# TK531_Utgangstrinn.net
KiCad netlist of a schematic drawn in Altium Designer
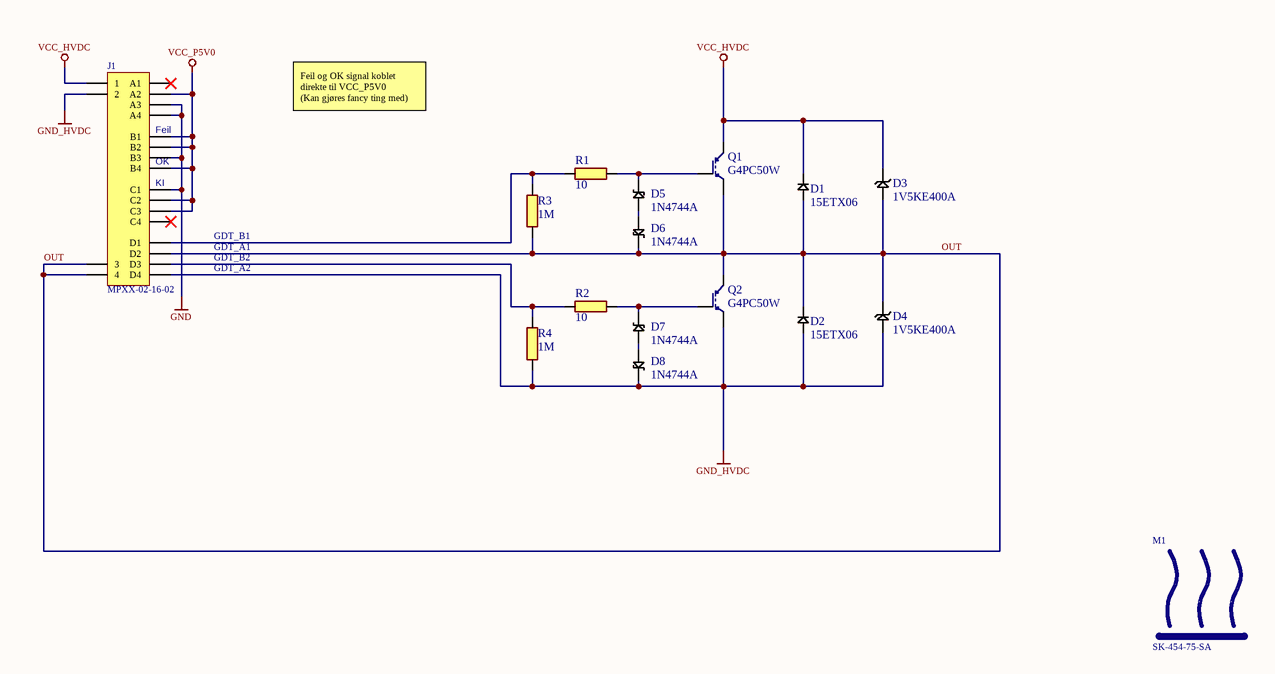
[diagram p0: TK531_Utgangstrinn.SchDoc]

(export (version "E")
  (design (tool "Eeschema 10.0.6"))
  (components
    (comp (ref "D1")
      (value "15ETX06")
      (footprint "TO-220-2P")
      (description "DIODE, HYPERFAST, 15A, 600V")
      (libsource (lib "OVLib_64") (part "Diode_3P"))
    )
    (comp (ref "D2")
      (value "15ETX06")
      (footprint "TO-220-2P")
      (description "DIODE, HYPERFAST, 15A, 600V")
      (libsource (lib "OVLib_64") (part "Diode_3P"))
    )
    (comp (ref "D3")
      (value "1V5KE400A")
      (footprint "DO-201")
      (description "TVS diode,  400V, 1500W")
      (libsource (lib "OVLib_64") (part "TVSDiode"))
    )
    (comp (ref "D4")
      (value "1V5KE400A")
      (footprint "DO-201")
      (description "TVS diode,  400V, 1500W")
      (libsource (lib "OVLib_64") (part "TVSDiode"))
    )
    (comp (ref "D5")
      (value "1N4744A")
      (footprint "DO-41")
      (description "Zenerdiode 15V 1.3W")
      (libsource (lib "OVLib_64") (part "Zenerdiode"))
    )
    (comp (ref "D6")
      (value "1N4744A")
      (footprint "DO-41")
      (description "Zenerdiode 15V 1.3W")
      (libsource (lib "OVLib_64") (part "Zenerdiode"))
    )
    (comp (ref "D7")
      (value "1N4744A")
      (footprint "DO-41")
      (description "Zenerdiode 15V 1.3W")
      (libsource (lib "OVLib_64") (part "Zenerdiode"))
    )
    (comp (ref "D8")
      (value "1N4744A")
      (footprint "DO-41")
      (description "Zenerdiode 15V 1.3W")
      (libsource (lib "OVLib_64") (part "Zenerdiode"))
    )
    (comp (ref "J1")
      (value "MPXX-02-16-02")
      (footprint "MPTC-02-16-02-01-03-L-RA-SD")
      (description "SAMTEC Connector")
      (libsource (lib "OVLib_64") (part "MPXX-02-16-02"))
    )
    (comp (ref "M1")
      (value "SK-454-75-SA")
      (footprint "SK-454-75-SA")
      (description "Heatsink")
      (libsource (lib "OVLib_64") (part "Heatsink"))
    )
    (comp (ref "Q1")
      (value "G4PC50W")
      (footprint "TO-247")
      (description "IGBT, 600V, 55A")
      (libsource (lib "OVLib_64") (part "G4PC50W"))
    )
    (comp (ref "Q2")
      (value "G4PC50W")
      (footprint "TO-247")
      (description "IGBT, 600V, 55A")
      (libsource (lib "OVLib_64") (part "G4PC50W"))
    )
    (comp (ref "R1")
      (value "10")
      (footprint "RESA_0.25W")
      (description "0.25W 1% Generic resistor")
      (libsource (lib "") (part "Resistor2_1"))
    )
    (comp (ref "R2")
      (value "10")
      (footprint "RESA_0.25W")
      (description "0.25W 1% Generic resistor")
      (libsource (lib "") (part "Resistor2_1"))
    )
    (comp (ref "R3")
      (value "1M")
      (footprint "RESC0603(1608)_N")
      (description "0.1W 1% Thick film resistor")
      (libsource (lib "OVLib_64") (part "Resistor2"))
    )
    (comp (ref "R4")
      (value "1M")
      (footprint "RESC0603(1608)_N")
      (description "0.1W 1% Thick film resistor")
      (libsource (lib "OVLib_64") (part "Resistor2"))
    )
  )
  (nets
    (net (code "1") (name "/OUT") (class "Default")
      (node (ref "D1") (pin "3") (pinfunction "A_3") (pintype "passive"))
      (node (ref "D2") (pin "1") (pinfunction "K_1") (pintype "passive"))
      (node (ref "D3") (pin "1") (pinfunction "A_1") (pintype "passive"))
      (node (ref "D4") (pin "2") (pinfunction "K_2") (pintype "passive"))
      (node (ref "D6") (pin "2") (pinfunction "K_2") (pintype "passive"))
      (node (ref "J1") (pin "18") (pinfunction "D2_18") (pintype "passive"))
      (node (ref "J1") (pin "3") (pinfunction "3_3") (pintype "passive"))
      (node (ref "J1") (pin "4") (pinfunction "4_4") (pintype "passive"))
      (node (ref "Q1") (pin "3") (pinfunction "E_3") (pintype "passive"))
      (node (ref "Q2") (pin "2") (pinfunction "C_2") (pintype "passive"))
      (node (ref "R3") (pin "1") (pinfunction "1_1") (pintype "passive"))
    )
    (net (code "2") (name "GND") (class "Default")
      (node (ref "J1") (pin "11") (pinfunction "B3_11") (pintype "passive"))
      (node (ref "J1") (pin "13") (pinfunction "C1_13") (pintype "passive"))
      (node (ref "J1") (pin "7") (pinfunction "A3_7") (pintype "passive"))
      (node (ref "J1") (pin "8") (pinfunction "A4_8") (pintype "passive"))
    )
    (net (code "3") (name "GND_HVDC") (class "Default")
      (node (ref "D2") (pin "3") (pinfunction "A_3") (pintype "passive"))
      (node (ref "D4") (pin "1") (pinfunction "A_1") (pintype "passive"))
      (node (ref "D8") (pin "2") (pinfunction "K_2") (pintype "passive"))
      (node (ref "J1") (pin "2") (pinfunction "2_2") (pintype "passive"))
      (node (ref "J1") (pin "20") (pinfunction "D4_20") (pintype "passive"))
      (node (ref "Q2") (pin "3") (pinfunction "E_3") (pintype "passive"))
      (node (ref "R4") (pin "1") (pinfunction "1_1") (pintype "passive"))
    )
    (net (code "4") (name "Net-(D5-A)") (class "Default")
      (node (ref "D5") (pin "1") (pinfunction "A_1") (pintype "passive"))
      (node (ref "D6") (pin "1") (pinfunction "A_1") (pintype "passive"))
    )
    (net (code "5") (name "Net-(D5-K)") (class "Default")
      (node (ref "D5") (pin "2") (pinfunction "K_2") (pintype "passive"))
      (node (ref "Q1") (pin "1") (pinfunction "G_1") (pintype "passive"))
      (node (ref "R1") (pin "2") (pinfunction "2_2") (pintype "passive"))
    )
    (net (code "6") (name "Net-(D7-A)") (class "Default")
      (node (ref "D7") (pin "1") (pinfunction "A_1") (pintype "passive"))
      (node (ref "D8") (pin "1") (pinfunction "A_1") (pintype "passive"))
    )
    (net (code "7") (name "Net-(D7-K)") (class "Default")
      (node (ref "D7") (pin "2") (pinfunction "K_2") (pintype "passive"))
      (node (ref "Q2") (pin "1") (pinfunction "G_1") (pintype "passive"))
      (node (ref "R2") (pin "2") (pinfunction "2_2") (pintype "passive"))
    )
    (net (code "8") (name "Net-(J1-D1)") (class "Default")
      (node (ref "J1") (pin "17") (pinfunction "D1_17") (pintype "passive"))
      (node (ref "R1") (pin "1") (pinfunction "1_1") (pintype "passive"))
      (node (ref "R3") (pin "2") (pinfunction "2_2") (pintype "passive"))
    )
    (net (code "9") (name "Net-(J1-D3)") (class "Default")
      (node (ref "J1") (pin "19") (pinfunction "D3_19") (pintype "passive"))
      (node (ref "R2") (pin "1") (pinfunction "1_1") (pintype "passive"))
      (node (ref "R4") (pin "2") (pinfunction "2_2") (pintype "passive"))
    )
    (net (code "10") (name "VCC_HVDC") (class "Default")
      (node (ref "D1") (pin "1") (pinfunction "K_1") (pintype "passive"))
      (node (ref "D3") (pin "2") (pinfunction "K_2") (pintype "passive"))
      (node (ref "J1") (pin "1") (pinfunction "1_1") (pintype "passive"))
      (node (ref "Q1") (pin "2") (pinfunction "C_2") (pintype "passive"))
    )
    (net (code "11") (name "VCC_P5V0") (class "Default")
      (node (ref "J1") (pin "10") (pinfunction "B2_10") (pintype "passive"))
      (node (ref "J1") (pin "12") (pinfunction "B4_12") (pintype "passive"))
      (node (ref "J1") (pin "14") (pinfunction "C2_14") (pintype "passive"))
      (node (ref "J1") (pin "15") (pinfunction "C3_15") (pintype "passive"))
      (node (ref "J1") (pin "6") (pinfunction "A2_6") (pintype "passive"))
      (node (ref "J1") (pin "9") (pinfunction "B1_9") (pintype "passive"))
    )
    (net (code "12") (name "unconnected-(J1-A1-Pad5)") (class "Default")
      (node (ref "J1") (pin "5") (pinfunction "A1_5") (pintype "passive+no_connect"))
    )
    (net (code "13") (name "unconnected-(J1-C4-Pad16)") (class "Default")
      (node (ref "J1") (pin "16") (pinfunction "C4_16") (pintype "passive+no_connect"))
    )
  )
)
